# esp-oled.net
KiCad netlist of a schematic drawn in EAGLE
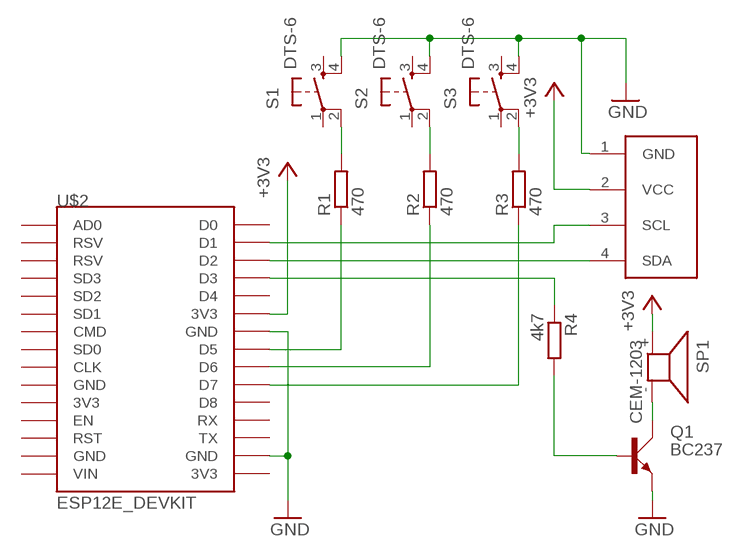
[diagram p0: schematic, sheet 1]

(export (version "E")
  (design (tool "Eeschema 10.0.6"))
  (components
    (comp (ref "Q1")
      (value "BC237")
      (footprint "eagle-import:SOT54A")
      (libsource (lib "eagle-import") (part "BC237"))
    )
    (comp (ref "R1")
      (value "470")
      (footprint "eagle-import:0207_10B")
      (libsource (lib "eagle-import") (part "R-EU_0207/10B"))
    )
    (comp (ref "R2")
      (value "470")
      (footprint "eagle-import:0207_10B")
      (libsource (lib "eagle-import") (part "R-EU_0207/10B"))
    )
    (comp (ref "R3")
      (value "470")
      (footprint "eagle-import:0207_10B")
      (libsource (lib "eagle-import") (part "R-EU_0207/10B"))
    )
    (comp (ref "R4")
      (value "4k7")
      (footprint "eagle-import:0207_10B")
      (libsource (lib "eagle-import") (part "R-EU_0207/10B"))
    )
    (comp (ref "S1")
      (value "DTS-6")
      (footprint "eagle-import:DTS-6")
      (libsource (lib "eagle-import") (part "DTS-6"))
    )
    (comp (ref "S2")
      (value "DTS-6")
      (footprint "eagle-import:DTS-6")
      (libsource (lib "eagle-import") (part "DTS-6"))
    )
    (comp (ref "S3")
      (value "DTS-6")
      (footprint "eagle-import:DTS-6")
      (libsource (lib "eagle-import") (part "DTS-6"))
    )
    (comp (ref "SP1")
      (value "CEM-1203")
      (footprint "eagle-import:KSS1201")
      (libsource (lib "eagle-import") (part "KSS1201"))
    )
    (comp (ref "U$1")
      (value "I2C_OLED")
      (footprint "eagle-import:I2C_OLED_PACKAGE")
      (libsource (lib "eagle-import") (part "I2C_OLED"))
    )
    (comp (ref "U$2")
      (value "ESP12E_DEVKIT")
      (footprint "eagle-import:ESP12E_DEVKIT")
      (libsource (lib "eagle-import") (part "ESP12E_DEVKIT"))
    )
  )
  (nets
    (net (code "1") (name "+3V3") (class "Default")
      (node (ref "SP1") (pin "+") (pinfunction "1_+") (pintype "passive"))
      (node (ref "U$1") (pin "2") (pinfunction "VCC_2") (pintype "power_in"))
      (node (ref "U$2") (pin "3V3@1") (pinfunction "3V3_3V3@1") (pintype "bidirectional"))
    )
    (net (code "2") (name "GND") (class "Default")
      (node (ref "Q1") (pin "E") (pinfunction "E_E") (pintype "passive"))
      (node (ref "S1") (pin "4") (pinfunction "4_4") (pintype "passive"))
      (node (ref "S2") (pin "4") (pinfunction "4_4") (pintype "passive"))
      (node (ref "S3") (pin "4") (pinfunction "4_4") (pintype "passive"))
      (node (ref "U$1") (pin "1") (pinfunction "GND_1") (pintype "power_in"))
      (node (ref "U$2") (pin "GND@2") (pinfunction "GND_GND@2") (pintype "bidirectional"))
      (node (ref "U$2") (pin "GND@3") (pinfunction "GND_GND@3") (pintype "bidirectional"))
    )
    (net (code "3") (name "Net-(Q1-PadB)") (class "Default")
      (node (ref "Q1") (pin "B") (pinfunction "B_B") (pintype "passive"))
      (node (ref "R4") (pin "2") (pinfunction "2_2") (pintype "passive"))
    )
    (net (code "4") (name "Net-(R1-Pad1)") (class "Default")
      (node (ref "R1") (pin "1") (pinfunction "1_1") (pintype "passive"))
      (node (ref "U$2") (pin "D5") (pinfunction "D5_D5") (pintype "bidirectional"))
    )
    (net (code "5") (name "Net-(R1-Pad2)") (class "Default")
      (node (ref "R1") (pin "2") (pinfunction "2_2") (pintype "passive"))
      (node (ref "S1") (pin "2") (pinfunction "2_2") (pintype "passive"))
    )
    (net (code "6") (name "Net-(R2-Pad1)") (class "Default")
      (node (ref "R2") (pin "1") (pinfunction "1_1") (pintype "passive"))
      (node (ref "U$2") (pin "D6") (pinfunction "D6_D6") (pintype "bidirectional"))
    )
    (net (code "7") (name "Net-(R2-Pad2)") (class "Default")
      (node (ref "R2") (pin "2") (pinfunction "2_2") (pintype "passive"))
      (node (ref "S2") (pin "2") (pinfunction "2_2") (pintype "passive"))
    )
    (net (code "8") (name "Net-(R3-Pad1)") (class "Default")
      (node (ref "R3") (pin "1") (pinfunction "1_1") (pintype "passive"))
      (node (ref "U$2") (pin "D7") (pinfunction "D7_D7") (pintype "bidirectional"))
    )
    (net (code "9") (name "Net-(R3-Pad2)") (class "Default")
      (node (ref "R3") (pin "2") (pinfunction "2_2") (pintype "passive"))
      (node (ref "S3") (pin "2") (pinfunction "2_2") (pintype "passive"))
    )
    (net (code "10") (name "Net-(R4-Pad1)") (class "Default")
      (node (ref "R4") (pin "1") (pinfunction "1_1") (pintype "passive"))
      (node (ref "U$2") (pin "D3") (pinfunction "D3_D3") (pintype "bidirectional"))
    )
    (net (code "11") (name "Net-(SP1-2)") (class "Default")
      (node (ref "Q1") (pin "C") (pinfunction "C_C") (pintype "passive"))
      (node (ref "SP1") (pin "-") (pinfunction "2_-") (pintype "passive"))
    )
    (net (code "12") (name "Net-(U$1-SCL)") (class "Default")
      (node (ref "U$1") (pin "3") (pinfunction "SCL_3") (pintype "bidirectional"))
      (node (ref "U$2") (pin "D1") (pinfunction "D1_D1") (pintype "bidirectional"))
    )
    (net (code "13") (name "Net-(U$1-SDA)") (class "Default")
      (node (ref "U$1") (pin "4") (pinfunction "SDA_4") (pintype "bidirectional"))
      (node (ref "U$2") (pin "D2") (pinfunction "D2_D2") (pintype "bidirectional"))
    )
    (net (code "14") (name "unconnected-(S1-Pad1)") (class "Default")
      (node (ref "S1") (pin "1") (pinfunction "1_1") (pintype "passive"))
    )
    (net (code "15") (name "unconnected-(S1-Pad3)") (class "Default")
      (node (ref "S1") (pin "3") (pinfunction "3_3") (pintype "passive"))
    )
    (net (code "16") (name "unconnected-(S2-Pad1)") (class "Default")
      (node (ref "S2") (pin "1") (pinfunction "1_1") (pintype "passive"))
    )
    (net (code "17") (name "unconnected-(S2-Pad3)") (class "Default")
      (node (ref "S2") (pin "3") (pinfunction "3_3") (pintype "passive"))
    )
    (net (code "18") (name "unconnected-(S3-Pad1)") (class "Default")
      (node (ref "S3") (pin "1") (pinfunction "1_1") (pintype "passive"))
    )
    (net (code "19") (name "unconnected-(S3-Pad3)") (class "Default")
      (node (ref "S3") (pin "3") (pinfunction "3_3") (pintype "passive"))
    )
    (net (code "20") (name "unconnected-(U$2-3V3-Pad3V3@0)") (class "Default")
      (node (ref "U$2") (pin "3V3@0") (pinfunction "3V3_3V3@0") (pintype "bidirectional"))
    )
    (net (code "21") (name "unconnected-(U$2-3V3-Pad3V3@2)") (class "Default")
      (node (ref "U$2") (pin "3V3@2") (pinfunction "3V3_3V3@2") (pintype "bidirectional"))
    )
    (net (code "22") (name "unconnected-(U$2-GND-PadGND@0)") (class "Default")
      (node (ref "U$2") (pin "GND@0") (pinfunction "GND_GND@0") (pintype "bidirectional"))
    )
    (net (code "23") (name "unconnected-(U$2-GND-PadGND@1)") (class "Default")
      (node (ref "U$2") (pin "GND@1") (pinfunction "GND_GND@1") (pintype "bidirectional"))
    )
    (net (code "24") (name "unconnected-(U$2-PadAD0)") (class "Default")
      (node (ref "U$2") (pin "AD0") (pinfunction "AD0_AD0") (pintype "bidirectional"))
    )
    (net (code "25") (name "unconnected-(U$2-PadCLK)") (class "Default")
      (node (ref "U$2") (pin "CLK") (pinfunction "CLK_CLK") (pintype "bidirectional"))
    )
    (net (code "26") (name "unconnected-(U$2-PadCMD)") (class "Default")
      (node (ref "U$2") (pin "CMD") (pinfunction "CMD_CMD") (pintype "bidirectional"))
    )
    (net (code "27") (name "unconnected-(U$2-PadD0)") (class "Default")
      (node (ref "U$2") (pin "D0") (pinfunction "D0_D0") (pintype "bidirectional"))
    )
    (net (code "28") (name "unconnected-(U$2-PadD4)") (class "Default")
      (node (ref "U$2") (pin "D4") (pinfunction "D4_D4") (pintype "bidirectional"))
    )
    (net (code "29") (name "unconnected-(U$2-PadD8)") (class "Default")
      (node (ref "U$2") (pin "D8") (pinfunction "D8_D8") (pintype "bidirectional"))
    )
    (net (code "30") (name "unconnected-(U$2-PadEN)") (class "Default")
      (node (ref "U$2") (pin "EN") (pinfunction "EN_EN") (pintype "bidirectional"))
    )
    (net (code "31") (name "unconnected-(U$2-PadRST)") (class "Default")
      (node (ref "U$2") (pin "RST") (pinfunction "RST_RST") (pintype "bidirectional"))
    )
    (net (code "32") (name "unconnected-(U$2-PadRX)") (class "Default")
      (node (ref "U$2") (pin "RX") (pinfunction "RX_RX") (pintype "bidirectional"))
    )
    (net (code "33") (name "unconnected-(U$2-PadSD0)") (class "Default")
      (node (ref "U$2") (pin "SD0") (pinfunction "SD0_SD0") (pintype "bidirectional"))
    )
    (net (code "34") (name "unconnected-(U$2-PadSD1)") (class "Default")
      (node (ref "U$2") (pin "SD1") (pinfunction "SD1_SD1") (pintype "bidirectional"))
    )
    (net (code "35") (name "unconnected-(U$2-PadSD2)") (class "Default")
      (node (ref "U$2") (pin "SD2") (pinfunction "SD2_SD2") (pintype "bidirectional"))
    )
    (net (code "36") (name "unconnected-(U$2-PadSD3)") (class "Default")
      (node (ref "U$2") (pin "SD3") (pinfunction "SD3_SD3") (pintype "bidirectional"))
    )
    (net (code "37") (name "unconnected-(U$2-PadTX)") (class "Default")
      (node (ref "U$2") (pin "TX") (pinfunction "TX_TX") (pintype "bidirectional"))
    )
    (net (code "38") (name "unconnected-(U$2-PadVIN)") (class "Default")
      (node (ref "U$2") (pin "VIN") (pinfunction "VIN_VIN") (pintype "bidirectional"))
    )
    (net (code "39") (name "unconnected-(U$2-RSV-PadRSV@0)") (class "Default")
      (node (ref "U$2") (pin "RSV@0") (pinfunction "RSV_RSV@0") (pintype "bidirectional"))
    )
    (net (code "40") (name "unconnected-(U$2-RSV-PadRSV@1)") (class "Default")
      (node (ref "U$2") (pin "RSV@1") (pinfunction "RSV_RSV@1") (pintype "bidirectional"))
    )
  )
)
